# GPS.net
KiCad netlist of a schematic drawn in Altium Designer
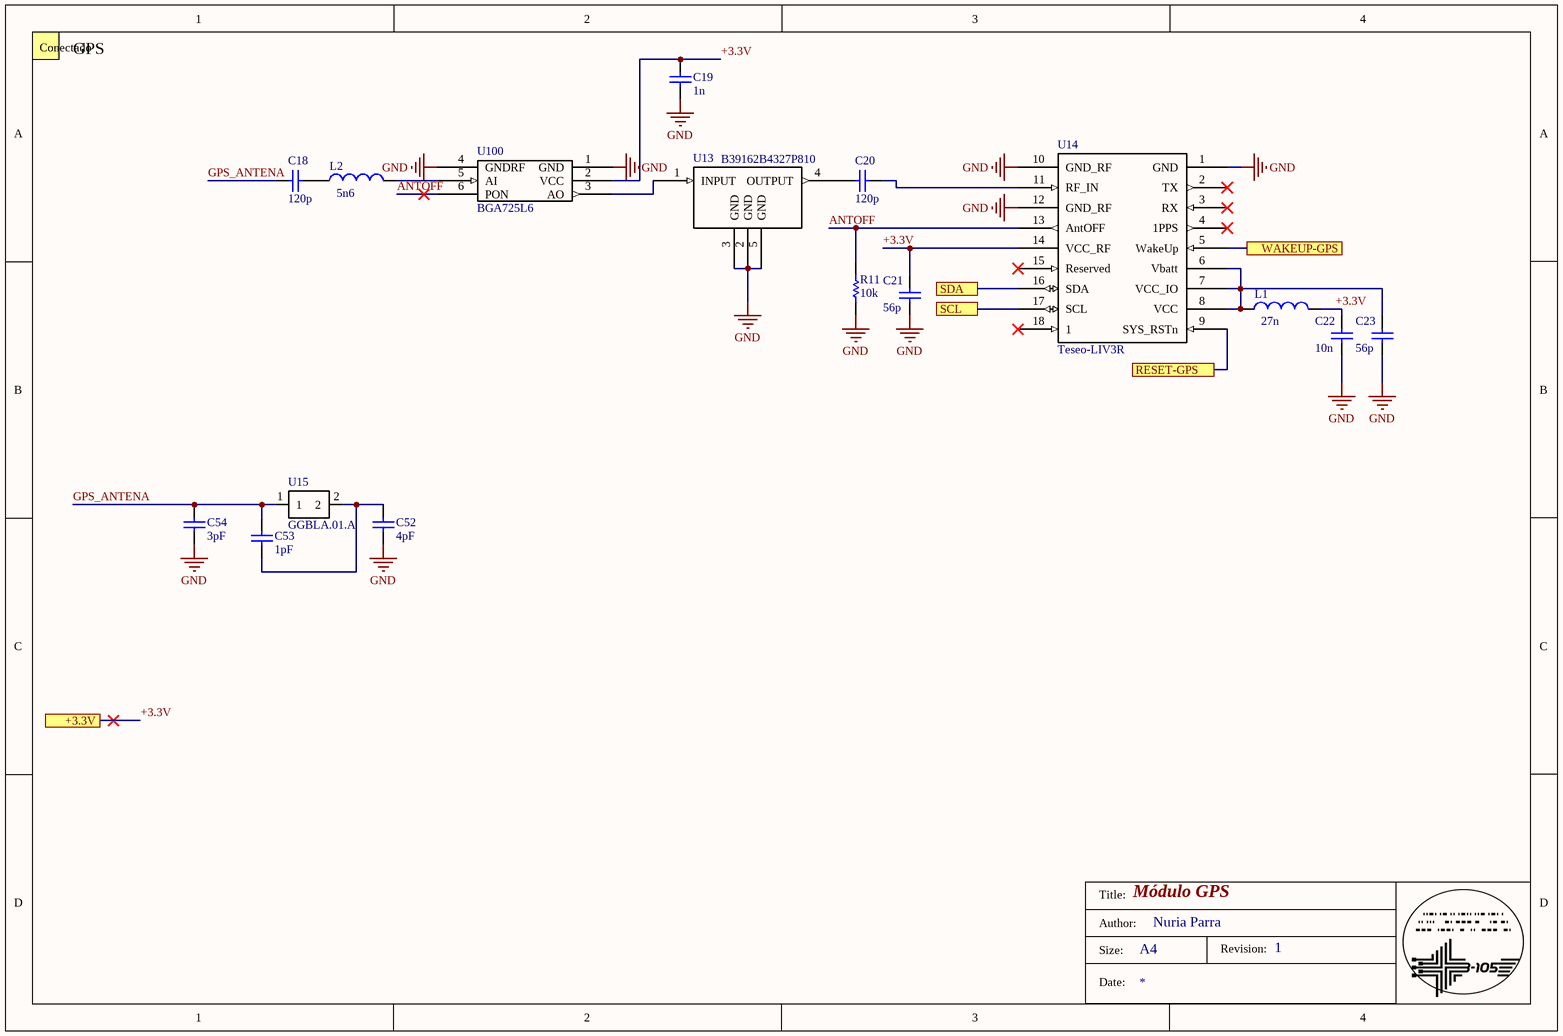
[diagram p0: GPS.SchDoc]

(export (version "E")
  (design (tool "Eeschema 10.0.6"))
  (components
    (comp (ref "C18")
      (value "120p")
      (footprint "0402 CAP")
      (fields (field (name "Comment") "Cap"))
      (libsource (lib "B105rlc") (part "Cap"))
    )
    (comp (ref "C19")
      (value "1n")
      (footprint "0402 CAP")
      (fields (field (name "Comment") "Cap"))
      (libsource (lib "B105rlc") (part "Cap"))
    )
    (comp (ref "C20")
      (value "120p")
      (footprint "0402 CAP")
      (fields (field (name "Comment") "Cap"))
      (libsource (lib "B105rlc") (part "Cap"))
    )
    (comp (ref "C21")
      (value "56p")
      (footprint "0201 CAP")
      (fields (field (name "Comment") "Cap"))
      (libsource (lib "B105rlc") (part "Cap"))
    )
    (comp (ref "C22")
      (value "10n")
      (footprint "0201 CAP")
      (fields (field (name "Comment") "Cap"))
      (libsource (lib "B105rlc") (part "Cap"))
    )
    (comp (ref "C23")
      (value "56p")
      (footprint "0201 CAP")
      (fields (field (name "Comment") "Cap"))
      (libsource (lib "B105rlc") (part "Cap"))
    )
    (comp (ref "C52")
      (value "4pF")
      (footprint "0402 CAP")
      (fields (field (name "Comment") "Cap"))
      (libsource (lib "B105rlc") (part "Cap"))
    )
    (comp (ref "C53")
      (value "1pF")
      (footprint "0402 CAP")
      (fields (field (name "Comment") "Cap"))
      (libsource (lib "B105rlc") (part "Cap"))
    )
    (comp (ref "C54")
      (value "3pF")
      (footprint "0402 CAP")
      (fields (field (name "Comment") "Cap"))
      (libsource (lib "B105rlc") (part "Cap"))
    )
    (comp (ref "L1")
      (value "27n")
      (footprint "0402 IND")
      (fields (field (name "Comment") "L?"))
      (libsource (lib "B105rlc") (part "Ind"))
    )
    (comp (ref "L2")
      (value "5n6")
      (footprint "0402 IND")
      (fields (field (name "Comment") "L?"))
      (libsource (lib "B105rlc") (part "Ind"))
    )
    (comp (ref "R11") (value "10k") (footprint "0402 RES") (libsource (lib "B105rlc") (part "Res")))
    (comp (ref "U13")
      (value "B39162B4327P810")
      (footprint "B39162B4327P810")
      (libsource (lib "Libreria Nuria") (part "B39162B4327P810"))
    )
    (comp (ref "U14") (value "Teseo-LIV3R") (footprint "GPS") (libsource (lib "Libreria Nuria") (part "GPS")))
    (comp (ref "U15")
      (value "GGBLA.01.A")
      (footprint "GGBLA.01.A")
      (libsource (lib "Libreria Nuria") (part "GGBLA.01.A"))
    )
    (comp (ref "U100")
      (value "BGA725L6")
      (footprint "BGA")
      (libsource (lib "Libreria Nuria") (part "BGA725L6"))
    )
  )
  (nets
    (net (code "1") (name "/+3.3V") (class "Default")
      (node (ref "C19") (pin "1") (pinfunction "1_1") (pintype "passive"))
      (node (ref "C21") (pin "2") (pinfunction "2_2") (pintype "passive"))
      (node (ref "C22") (pin "2") (pinfunction "2_2") (pintype "passive"))
      (node (ref "L1") (pin "2") (pinfunction "2_2") (pintype "passive"))
      (node (ref "U100") (pin "2") (pinfunction "VCC_2") (pintype "open_emitter"))
      (node (ref "U14") (pin "14") (pinfunction "VCC_RF_14") (pintype "power_in"))
    )
    (net (code "2") (name "/ANTOFF") (class "Default")
      (node (ref "R11") (pin "2") (pinfunction "2_2") (pintype "passive"))
      (node (ref "U100") (pin "6") (pinfunction "PON_6") (pintype "power_in"))
      (node (ref "U14") (pin "13") (pinfunction "AntOFF_13") (pintype "output"))
    )
    (net (code "3") (name "/GPS_ANTENA") (class "Default")
      (node (ref "C18") (pin "2") (pinfunction "2_2") (pintype "passive"))
      (node (ref "C53") (pin "1") (pinfunction "1_1") (pintype "passive"))
      (node (ref "C54") (pin "1") (pinfunction "1_1") (pintype "passive"))
      (node (ref "U15") (pin "1") (pinfunction "1_1") (pintype "passive"))
    )
    (net (code "4") (name "/RESET-GPS") (class "Default")
      (node (ref "U14") (pin "9") (pinfunction "SYS_RSTn_9") (pintype "input"))
    )
    (net (code "5") (name "/SCL") (class "Default")
      (node (ref "U14") (pin "17") (pinfunction "SCL_17") (pintype "bidirectional"))
    )
    (net (code "6") (name "/SDA") (class "Default")
      (node (ref "U14") (pin "16") (pinfunction "SDA_16") (pintype "bidirectional"))
    )
    (net (code "7") (name "/WAKEUP-GPS") (class "Default")
      (node (ref "U14") (pin "5") (pinfunction "WakeUp_5") (pintype "input"))
    )
    (net (code "8") (name "GND") (class "Default")
      (node (ref "C19") (pin "2") (pinfunction "2_2") (pintype "passive"))
      (node (ref "C21") (pin "1") (pinfunction "1_1") (pintype "passive"))
      (node (ref "C22") (pin "1") (pinfunction "1_1") (pintype "passive"))
      (node (ref "C23") (pin "1") (pinfunction "1_1") (pintype "passive"))
      (node (ref "C52") (pin "2") (pinfunction "2_2") (pintype "passive"))
      (node (ref "C54") (pin "2") (pinfunction "2_2") (pintype "passive"))
      (node (ref "R11") (pin "1") (pinfunction "1_1") (pintype "passive"))
      (node (ref "U100") (pin "1") (pinfunction "GND_1") (pintype "power_in"))
      (node (ref "U100") (pin "4") (pinfunction "GNDRF_4") (pintype "power_in"))
      (node (ref "U13") (pin "2") (pinfunction "GND_2") (pintype "power_in"))
      (node (ref "U13") (pin "3") (pinfunction "GND_3") (pintype "power_in"))
      (node (ref "U13") (pin "5") (pinfunction "GND_5") (pintype "power_in"))
      (node (ref "U14") (pin "1") (pinfunction "GND_1") (pintype "power_in"))
      (node (ref "U14") (pin "10") (pinfunction "GND_RF_10") (pintype "power_in"))
      (node (ref "U14") (pin "12") (pinfunction "GND_RF_12") (pintype "power_in"))
    )
    (net (code "9") (name "Net-(C18-Pad1)") (class "Default")
      (node (ref "C18") (pin "1") (pinfunction "1_1") (pintype "passive"))
      (node (ref "L2") (pin "1") (pinfunction "1_1") (pintype "passive"))
    )
    (net (code "10") (name "Net-(C52-Pad1)") (class "Default")
      (node (ref "C52") (pin "1") (pinfunction "1_1") (pintype "passive"))
      (node (ref "C53") (pin "2") (pinfunction "2_2") (pintype "passive"))
      (node (ref "U15") (pin "2") (pinfunction "2_2") (pintype "passive"))
    )
    (net (code "11") (name "Net-(U13-OUTPUT)") (class "Default")
      (node (ref "C20") (pin "1") (pinfunction "1_1") (pintype "passive"))
      (node (ref "U13") (pin "4") (pinfunction "OUTPUT_4") (pintype "output"))
    )
    (net (code "12") (name "Net-(U14-RF_IN)") (class "Default")
      (node (ref "C20") (pin "2") (pinfunction "2_2") (pintype "passive"))
      (node (ref "U14") (pin "11") (pinfunction "RF_IN_11") (pintype "input"))
    )
    (net (code "13") (name "Net-(U14-VCC)") (class "Default")
      (node (ref "C23") (pin "2") (pinfunction "2_2") (pintype "passive"))
      (node (ref "L1") (pin "1") (pinfunction "1_1") (pintype "passive"))
      (node (ref "U14") (pin "6") (pinfunction "Vbatt_6") (pintype "power_in"))
      (node (ref "U14") (pin "7") (pinfunction "VCC_IO_7") (pintype "power_in"))
      (node (ref "U14") (pin "8") (pinfunction "VCC_8") (pintype "power_in"))
    )
    (net (code "14") (name "Net-(U100-AI)") (class "Default")
      (node (ref "L2") (pin "2") (pinfunction "2_2") (pintype "passive"))
      (node (ref "U100") (pin "5") (pinfunction "AI_5") (pintype "input"))
    )
    (net (code "15") (name "Net-(U100-AO)") (class "Default")
      (node (ref "U100") (pin "3") (pinfunction "AO_3") (pintype "output"))
      (node (ref "U13") (pin "1") (pinfunction "INPUT_1") (pintype "input"))
    )
    (net (code "16") (name "unconnected-(U14-1-Pad18)") (class "Default")
      (node (ref "U14") (pin "18") (pinfunction "1_18") (pintype "input+no_connect"))
    )
    (net (code "17") (name "unconnected-(U14-1PPS-Pad4)") (class "Default")
      (node (ref "U14") (pin "4") (pinfunction "1PPS_4") (pintype "output+no_connect"))
    )
    (net (code "18") (name "unconnected-(U14-RX-Pad3)") (class "Default")
      (node (ref "U14") (pin "3") (pinfunction "RX_3") (pintype "input+no_connect"))
    )
    (net (code "19") (name "unconnected-(U14-Reserved-Pad15)") (class "Default")
      (node (ref "U14") (pin "15") (pinfunction "Reserved_15") (pintype "input+no_connect"))
    )
    (net (code "20") (name "unconnected-(U14-TX-Pad2)") (class "Default")
      (node (ref "U14") (pin "2") (pinfunction "TX_2") (pintype "output+no_connect"))
    )
  )
)
